# WT2_Screen.net
KiCad netlist of a schematic drawn in Altium Designer
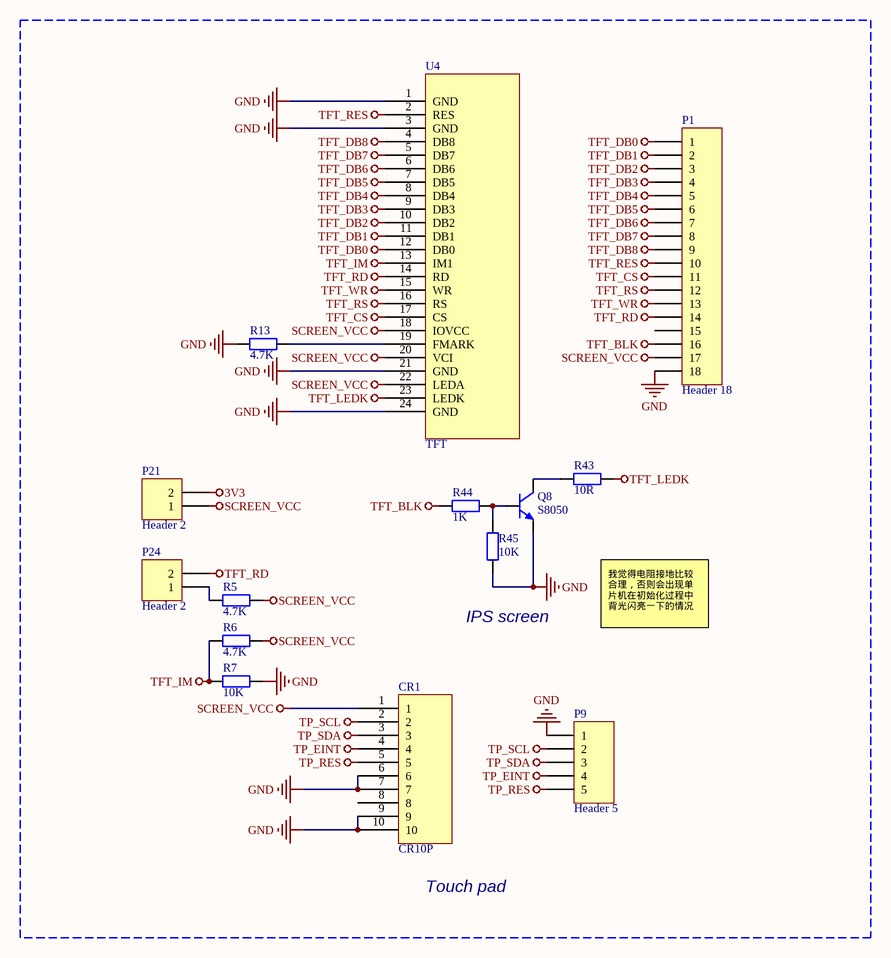
[diagram p0: WT2_Screen.SchDoc]

(export (version "E")
  (design (tool "Eeschema 10.0.6"))
  (components
    (comp (ref "CR1")
      (value "CR10P")
      (footprint "TriggersLib:CONN RCPT 10POS 0.4MM")
      (description "板对板连接器")
      (libsource (lib "TriggersLib") (part "CONN RCPT 10P"))
    )
    (comp (ref "P1")
      (value "Header 18")
      (footprint "HDR1X18")
      (description "Header, 18-Pin")
      (fields (field (name "PUBLISHER") "Altium Limited"))
      (libsource (lib "Miscellaneous Connectors") (part "Header 18"))
    )
    (comp (ref "P9")
      (value "Header 5")
      (footprint "HDR1X5")
      (description "Header, 5-Pin")
      (fields (field (name "PUBLISHER") "Altium Limited"))
      (libsource (lib "Miscellaneous Connectors") (part "Header 5"))
    )
    (comp (ref "P21")
      (value "Header 2")
      (footprint "HDR1X2")
      (description "Header, 2-Pin")
      (fields (field (name "PUBLISHER") "Altium Limited"))
      (libsource (lib "Miscellaneous Connectors") (part "Header 2"))
    )
    (comp (ref "P24")
      (value "Header 2")
      (footprint "HDR1X2")
      (description "Header, 2-Pin")
      (fields (field (name "PUBLISHER") "Altium Limited"))
      (libsource (lib "Miscellaneous Connectors") (part "Header 2"))
    )
    (comp (ref "Q8")
      (value "S8050")
      (footprint "三极管_SOT-23")
      (fields (field (name "_MODEL") "S8050"))
      (libsource (lib "元件库") (part "Triode-NPN"))
    )
    (comp (ref "R5")
      (value "4.7K")
      (footprint "电阻_R0603")
      (fields (field (name "_VALUE") "4.7K"))
      (libsource (lib "") (part "Res_1"))
    )
    (comp (ref "R6")
      (value "4.7K")
      (footprint "电阻_R0603")
      (fields (field (name "_VALUE") "4.7K"))
      (libsource (lib "") (part "Res_1"))
    )
    (comp (ref "R7")
      (value "10K")
      (footprint "电阻_R0603")
      (fields (field (name "_VALUE") "10K"))
      (libsource (lib "") (part "Res_2"))
    )
    (comp (ref "R13")
      (value "4.7K")
      (footprint "电阻_R0603")
      (fields (field (name "_VALUE") "4.7K"))
      (libsource (lib "") (part "Res_1"))
    )
    (comp (ref "R43")
      (value "10R")
      (footprint "电阻_R0603")
      (fields (field (name "_VALUE") "10R"))
      (libsource (lib "") (part "Res_1"))
    )
    (comp (ref "R44")
      (value "1K")
      (footprint "电阻_R0603")
      (fields (field (name "_VALUE") "1K"))
      (libsource (lib "") (part "Res_1"))
    )
    (comp (ref "R45")
      (value "10K")
      (footprint "电阻_R0603")
      (fields (field (name "_VALUE") "10K"))
      (libsource (lib "元件库") (part "Res"))
    )
    (comp (ref "U4")
      (value "TFT")
      (footprint "TriggersLib:CONN-SMD_DF37NC-24DS-0.4V(51)")
      (libsource (lib "TriggersLib") (part "TFT_IPS_8Bit_1.54_240*240"))
    )
  )
  (nets
    (net (code "1") (name "3V3") (class "Default")
      (node (ref "P21") (pin "2") (pinfunction "2_2") (pintype "passive"))
    )
    (net (code "2") (name "GND") (class "Default")
      (node (ref "CR1") (pin "10") (pinfunction "10_10") (pintype "passive"))
      (node (ref "CR1") (pin "6") (pinfunction "6_6") (pintype "passive"))
      (node (ref "CR1") (pin "7") (pinfunction "7_7") (pintype "passive"))
      (node (ref "CR1") (pin "9") (pinfunction "9_9") (pintype "passive"))
      (node (ref "P1") (pin "18") (pinfunction "18_18") (pintype "passive"))
      (node (ref "P9") (pin "1") (pinfunction "1_1") (pintype "passive"))
      (node (ref "Q8") (pin "3") (pinfunction "E_3") (pintype "passive"))
      (node (ref "R13") (pin "1") (pinfunction "1_1") (pintype "passive"))
      (node (ref "R45") (pin "1") (pinfunction "1_1") (pintype "passive"))
      (node (ref "R7") (pin "1") (pinfunction "1_1") (pintype "passive"))
      (node (ref "U4") (pin "1") (pinfunction "GND_1") (pintype "passive"))
      (node (ref "U4") (pin "21") (pinfunction "GND_21") (pintype "passive"))
      (node (ref "U4") (pin "24") (pinfunction "GND_24") (pintype "passive"))
      (node (ref "U4") (pin "3") (pinfunction "GND_3") (pintype "passive"))
    )
    (net (code "3") (name "Net-(P24-Pad1)") (class "Default")
      (node (ref "P24") (pin "1") (pinfunction "1_1") (pintype "passive"))
      (node (ref "R5") (pin "1") (pinfunction "1_1") (pintype "passive"))
    )
    (net (code "4") (name "Net-(Q8-B)") (class "Default")
      (node (ref "Q8") (pin "1") (pinfunction "B_1") (pintype "passive"))
      (node (ref "R44") (pin "2") (pinfunction "2_2") (pintype "passive"))
      (node (ref "R45") (pin "2") (pinfunction "2_2") (pintype "passive"))
    )
    (net (code "5") (name "Net-(Q8-C)") (class "Default")
      (node (ref "Q8") (pin "2") (pinfunction "C_2") (pintype "passive"))
      (node (ref "R43") (pin "1") (pinfunction "1_1") (pintype "passive"))
    )
    (net (code "6") (name "Net-(U4-FMARK)") (class "Default")
      (node (ref "R13") (pin "2") (pinfunction "2_2") (pintype "passive"))
      (node (ref "U4") (pin "19") (pinfunction "FMARK_19") (pintype "passive"))
    )
    (net (code "7") (name "SCREEN_VCC") (class "Default")
      (node (ref "CR1") (pin "1") (pinfunction "1_1") (pintype "passive"))
      (node (ref "P1") (pin "17") (pinfunction "17_17") (pintype "passive"))
      (node (ref "P21") (pin "1") (pinfunction "1_1") (pintype "passive"))
      (node (ref "R5") (pin "2") (pinfunction "2_2") (pintype "passive"))
      (node (ref "R6") (pin "2") (pinfunction "2_2") (pintype "passive"))
      (node (ref "U4") (pin "18") (pinfunction "IOVCC_18") (pintype "passive"))
      (node (ref "U4") (pin "20") (pinfunction "VCI_20") (pintype "passive"))
      (node (ref "U4") (pin "22") (pinfunction "LEDA_22") (pintype "passive"))
    )
    (net (code "8") (name "TFT_BLK") (class "Default")
      (node (ref "P1") (pin "16") (pinfunction "16_16") (pintype "passive"))
      (node (ref "R44") (pin "1") (pinfunction "1_1") (pintype "passive"))
    )
    (net (code "9") (name "TFT_CS") (class "Default")
      (node (ref "P1") (pin "11") (pinfunction "11_11") (pintype "passive"))
      (node (ref "U4") (pin "17") (pinfunction "CS_17") (pintype "passive"))
    )
    (net (code "10") (name "TFT_DB0") (class "Default")
      (node (ref "P1") (pin "1") (pinfunction "1_1") (pintype "passive"))
      (node (ref "U4") (pin "12") (pinfunction "DB0_12") (pintype "passive"))
    )
    (net (code "11") (name "TFT_DB1") (class "Default")
      (node (ref "P1") (pin "2") (pinfunction "2_2") (pintype "passive"))
      (node (ref "U4") (pin "11") (pinfunction "DB1_11") (pintype "passive"))
    )
    (net (code "12") (name "TFT_DB2") (class "Default")
      (node (ref "P1") (pin "3") (pinfunction "3_3") (pintype "passive"))
      (node (ref "U4") (pin "10") (pinfunction "DB2_10") (pintype "passive"))
    )
    (net (code "13") (name "TFT_DB3") (class "Default")
      (node (ref "P1") (pin "4") (pinfunction "4_4") (pintype "passive"))
      (node (ref "U4") (pin "9") (pinfunction "DB3_9") (pintype "passive"))
    )
    (net (code "14") (name "TFT_DB4") (class "Default")
      (node (ref "P1") (pin "5") (pinfunction "5_5") (pintype "passive"))
      (node (ref "U4") (pin "8") (pinfunction "DB4_8") (pintype "passive"))
    )
    (net (code "15") (name "TFT_DB5") (class "Default")
      (node (ref "P1") (pin "6") (pinfunction "6_6") (pintype "passive"))
      (node (ref "U4") (pin "7") (pinfunction "DB5_7") (pintype "passive"))
    )
    (net (code "16") (name "TFT_DB6") (class "Default")
      (node (ref "P1") (pin "7") (pinfunction "7_7") (pintype "passive"))
      (node (ref "U4") (pin "6") (pinfunction "DB6_6") (pintype "passive"))
    )
    (net (code "17") (name "TFT_DB7") (class "Default")
      (node (ref "P1") (pin "8") (pinfunction "8_8") (pintype "passive"))
      (node (ref "U4") (pin "5") (pinfunction "DB7_5") (pintype "passive"))
    )
    (net (code "18") (name "TFT_DB8") (class "Default")
      (node (ref "P1") (pin "9") (pinfunction "9_9") (pintype "passive"))
      (node (ref "U4") (pin "4") (pinfunction "DB8_4") (pintype "passive"))
    )
    (net (code "19") (name "TFT_IM") (class "Default")
      (node (ref "R6") (pin "1") (pinfunction "1_1") (pintype "passive"))
      (node (ref "R7") (pin "2") (pinfunction "2_2") (pintype "passive"))
      (node (ref "U4") (pin "13") (pinfunction "IM1_13") (pintype "passive"))
    )
    (net (code "20") (name "TFT_LEDK") (class "Default")
      (node (ref "R43") (pin "2") (pinfunction "2_2") (pintype "passive"))
      (node (ref "U4") (pin "23") (pinfunction "LEDK_23") (pintype "passive"))
    )
    (net (code "21") (name "TFT_RD") (class "Default")
      (node (ref "P1") (pin "14") (pinfunction "14_14") (pintype "passive"))
      (node (ref "P24") (pin "2") (pinfunction "2_2") (pintype "passive"))
      (node (ref "U4") (pin "14") (pinfunction "RD_14") (pintype "passive"))
    )
    (net (code "22") (name "TFT_RES") (class "Default")
      (node (ref "P1") (pin "10") (pinfunction "10_10") (pintype "passive"))
      (node (ref "U4") (pin "2") (pinfunction "RES_2") (pintype "passive"))
    )
    (net (code "23") (name "TFT_RS") (class "Default")
      (node (ref "P1") (pin "12") (pinfunction "12_12") (pintype "passive"))
      (node (ref "U4") (pin "16") (pinfunction "RS_16") (pintype "passive"))
    )
    (net (code "24") (name "TFT_WR") (class "Default")
      (node (ref "P1") (pin "13") (pinfunction "13_13") (pintype "passive"))
      (node (ref "U4") (pin "15") (pinfunction "WR_15") (pintype "passive"))
    )
    (net (code "25") (name "TP_EINT") (class "Default")
      (node (ref "CR1") (pin "4") (pinfunction "4_4") (pintype "passive"))
      (node (ref "P9") (pin "4") (pinfunction "4_4") (pintype "passive"))
    )
    (net (code "26") (name "TP_RES") (class "Default")
      (node (ref "CR1") (pin "5") (pinfunction "5_5") (pintype "passive"))
      (node (ref "P9") (pin "5") (pinfunction "5_5") (pintype "passive"))
    )
    (net (code "27") (name "TP_SCL") (class "Default")
      (node (ref "CR1") (pin "2") (pinfunction "2_2") (pintype "passive"))
      (node (ref "P9") (pin "2") (pinfunction "2_2") (pintype "passive"))
    )
    (net (code "28") (name "TP_SDA") (class "Default")
      (node (ref "CR1") (pin "3") (pinfunction "3_3") (pintype "passive"))
      (node (ref "P9") (pin "3") (pinfunction "3_3") (pintype "passive"))
    )
    (net (code "29") (name "unconnected-(CR1-Pad8)") (class "Default")
      (node (ref "CR1") (pin "8") (pinfunction "8_8") (pintype "passive"))
    )
    (net (code "30") (name "unconnected-(P1-Pad15)") (class "Default")
      (node (ref "P1") (pin "15") (pinfunction "15_15") (pintype "passive"))
    )
  )
)
